# Sheet2.net
KiCad netlist of a schematic drawn in Altium Designer
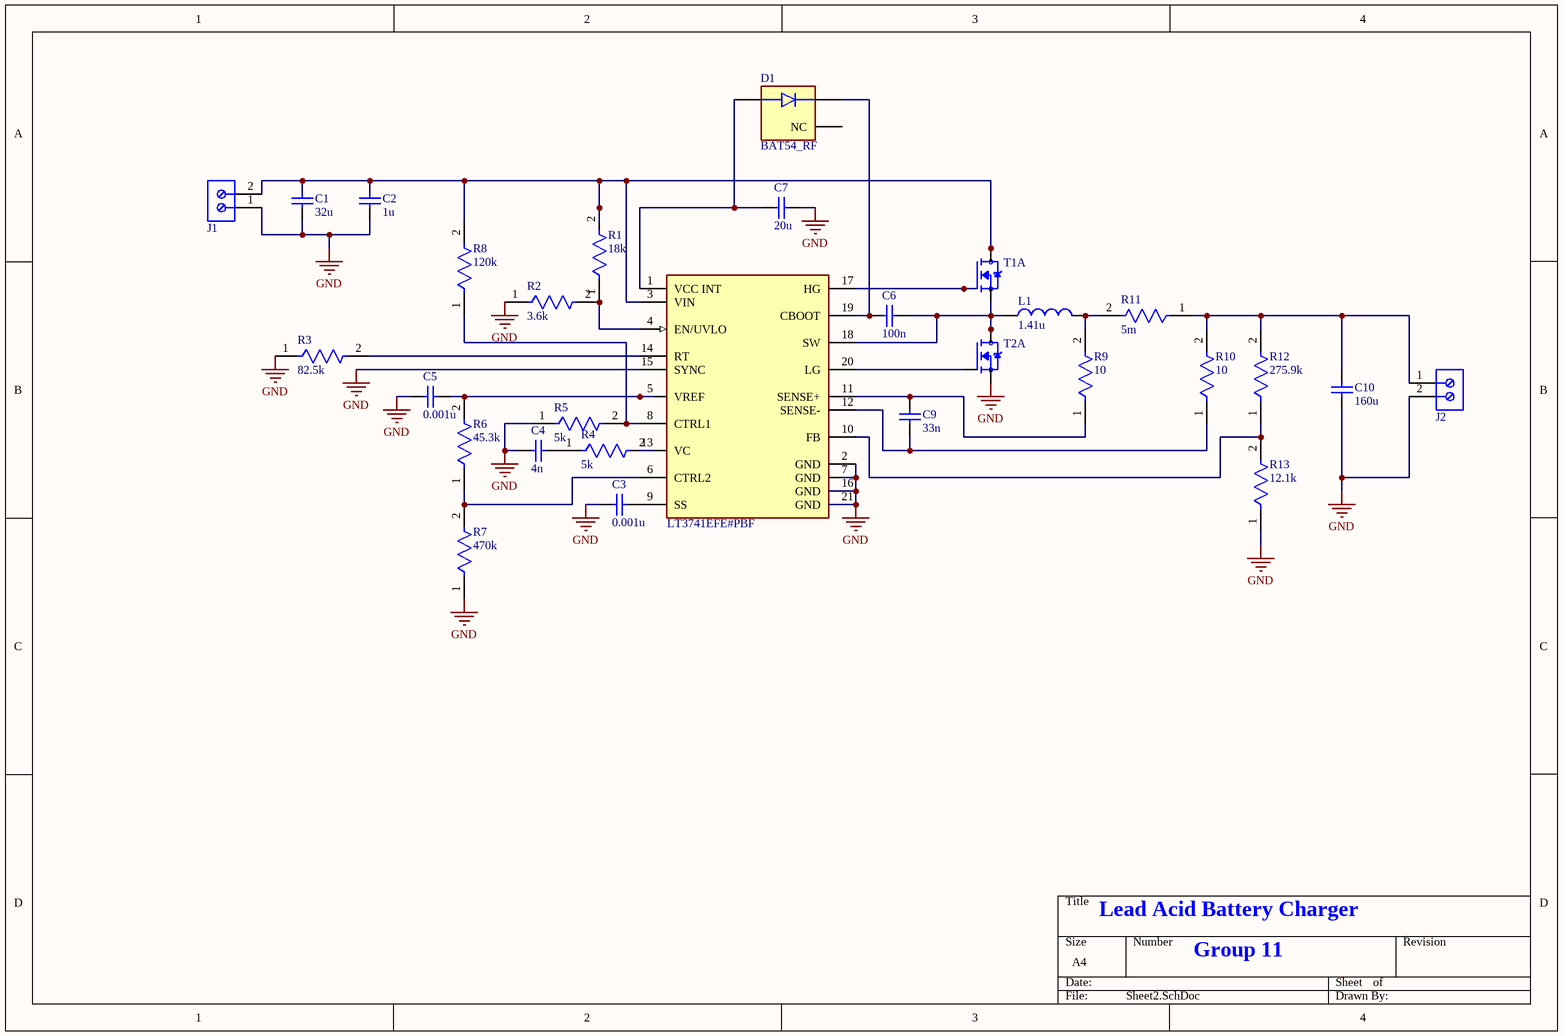
[diagram p0: Sheet2.SchDoc]

(export (version "E")
  (design (tool "Eeschema 10.0.6"))
  (components
    (comp (ref "C1")
      (value "C315C100J2G5TA")
      (footprint "KEMT-C315-THT-2")
      (description "Capacitor, Ceramic, 10 pF, +/-5 %, 200 V, 2-Pin THD, RoHS, Bulk")
      (fields (field (name "CAPACITANCE") "32u"))
      (libsource (lib "Altium Content Vault") (part "CAP-NP-2"))
    )
    (comp (ref "C2")
      (value "C315C100J2G5TA")
      (footprint "KEMT-C315-THT-2")
      (description "Capacitor, Ceramic, 10 pF, +/-5 %, 200 V, 2-Pin THD, RoHS, Bulk")
      (fields (field (name "CAPACITANCE") "1u"))
      (libsource (lib "Altium Content Vault") (part "CAP-NP-2"))
    )
    (comp (ref "C3")
      (value "C315C100J2G5TA")
      (footprint "KEMT-C315-THT-2")
      (description "Capacitor, Ceramic, 10 pF, +/-5 %, 200 V, 2-Pin THD, RoHS, Bulk")
      (fields (field (name "CAPACITANCE") "0.001u"))
      (libsource (lib "Altium Content Vault") (part "CAP-NP-2"))
    )
    (comp (ref "C4")
      (value "C315C100J2G5TA")
      (footprint "KEMT-C315-THT-2")
      (description "Capacitor, Ceramic, 10 pF, +/-5 %, 200 V, 2-Pin THD, RoHS, Bulk")
      (fields (field (name "CAPACITANCE") "4n"))
      (libsource (lib "Altium Content Vault") (part "CAP-NP-2"))
    )
    (comp (ref "C5")
      (value "C315C100J2G5TA")
      (footprint "KEMT-C315-THT-2")
      (description "Capacitor, Ceramic, 10 pF, +/-5 %, 200 V, 2-Pin THD, RoHS, Bulk")
      (fields (field (name "CAPACITANCE") "0.001u"))
      (libsource (lib "Altium Content Vault") (part "CAP-NP-2"))
    )
    (comp (ref "C6")
      (value "C315C100J2G5TA")
      (footprint "KEMT-C315-THT-2")
      (description "Capacitor, Ceramic, 10 pF, +/-5 %, 200 V, 2-Pin THD, RoHS, Bulk")
      (fields (field (name "CAPACITANCE") "100n"))
      (libsource (lib "Altium Content Vault") (part "CAP-NP-2"))
    )
    (comp (ref "C7")
      (value "C315C100J2G5TA")
      (footprint "KEMT-C315-THT-2")
      (description "Capacitor, Ceramic, 10 pF, +/-5 %, 200 V, 2-Pin THD, RoHS, Bulk")
      (fields (field (name "CAPACITANCE") "20u"))
      (libsource (lib "Altium Content Vault") (part "CAP-NP-2"))
    )
    (comp (ref "C9")
      (value "C315C100J2G5TA")
      (footprint "KEMT-C315-THT-2")
      (description "Capacitor, Ceramic, 10 pF, +/-5 %, 200 V, 2-Pin THD, RoHS, Bulk")
      (fields (field (name "CAPACITANCE") "33n"))
      (libsource (lib "Altium Content Vault") (part "CAP-NP-2"))
    )
    (comp (ref "C10")
      (value "C315C100J2G5TA")
      (footprint "KEMT-C315-THT-2")
      (description "Capacitor, Ceramic, 10 pF, +/-5 %, 200 V, 2-Pin THD, RoHS, Bulk")
      (fields (field (name "CAPACITANCE") "160u"))
      (libsource (lib "Altium Content Vault") (part "CAP-NP-2"))
    )
    (comp (ref "D1")
      (value "BAT54_RF")
      (footprint "SOT95P237X112-3N")
      (libsource (lib "BAT54_RF") (part "BAT54_RF"))
    )
    (comp (ref "J1")
      (value "1725656")
      (footprint "PHOE-1725656-2")
      (description "Male Header, Pitch 2.54 mm, 1 x 2 Position, Height 9 mm, Tail Length 3.5 mm")
      (fields (field (name "MANUFACTURER") "Phoenix Contact"))
      (libsource (lib "Altium Content Vault") (part "CN-1P-F-TB2"))
    )
    (comp (ref "J2")
      (value "1725656")
      (footprint "PHOE-1725656-2")
      (description "Male Header, Pitch 2.54 mm, 1 x 2 Position, Height 9 mm, Tail Length 3.5 mm")
      (fields (field (name "MANUFACTURER") "Phoenix Contact"))
      (libsource (lib "Altium Content Vault") (part "CN-1P-F-TB2"))
    )
    (comp (ref "L1")
      (value "7443551131")
      (footprint "IND_7443551131")
      (description "13ÂµH Shielded Wirewound Inductor 10A 11.2mOhm Nonstandard")
      (fields (field (name "MF") "Wurth Electronics") (field (name "INDUCTANCE") "1.41u"))
      (libsource (lib "7443551131") (part "7443551131"))
    )
    (comp (ref "q2etpo")
      (value "LT3741EFE#PBF")
      (footprint "FP-FE-20-05-08-1663-CB-IPC_C")
      (description "IC REG CTRLR BUCK 20TSSOP")
      (libsource (lib "Altium Content Vault") (part "060a2fb32948f8c97f943a762166035"))
    )
    (comp (ref "R1")
      (value "15FR010E")
      (footprint "FP-15FR010E-MFG")
      (description "RES 0.01 OHM 5W 1% AXIAL")
      (fields (field (name "RESISTANCE") "18k") (field (name "TOLERANCE") "1%"))
      (libsource (lib "Altium Content Vault") (part "1029c3af85768c4190bb7ad29bc67b5"))
    )
    (comp (ref "R2")
      (value "15FR010E")
      (footprint "FP-15FR010E-MFG")
      (description "RES 0.01 OHM 5W 1% AXIAL")
      (fields (field (name "RESISTANCE") "3.6k") (field (name "TOLERANCE") "1%"))
      (libsource (lib "Altium Content Vault") (part "1029c3af85768c4190bb7ad29bc67b5"))
    )
    (comp (ref "R3")
      (value "15FR010E")
      (footprint "FP-15FR010E-MFG")
      (description "RES 0.01 OHM 5W 1% AXIAL")
      (fields (field (name "RESISTANCE") "82.5k") (field (name "TOLERANCE") "1%"))
      (libsource (lib "Altium Content Vault") (part "1029c3af85768c4190bb7ad29bc67b5"))
    )
    (comp (ref "R4")
      (value "15FR010E")
      (footprint "FP-15FR010E-MFG")
      (description "RES 0.01 OHM 5W 1% AXIAL")
      (fields (field (name "RESISTANCE") "5k") (field (name "TOLERANCE") "1%"))
      (libsource (lib "Altium Content Vault") (part "1029c3af85768c4190bb7ad29bc67b5"))
    )
    (comp (ref "R5")
      (value "15FR010E")
      (footprint "FP-15FR010E-MFG")
      (description "RES 0.01 OHM 5W 1% AXIAL")
      (fields (field (name "RESISTANCE") "5k") (field (name "TOLERANCE") "1%"))
      (libsource (lib "Altium Content Vault") (part "1029c3af85768c4190bb7ad29bc67b5"))
    )
    (comp (ref "R6")
      (value "15FR010E")
      (footprint "FP-15FR010E-MFG")
      (description "RES 0.01 OHM 5W 1% AXIAL")
      (fields (field (name "RESISTANCE") "45.3k") (field (name "TOLERANCE") "1%"))
      (libsource (lib "Altium Content Vault") (part "1029c3af85768c4190bb7ad29bc67b5"))
    )
    (comp (ref "R7")
      (value "15FR010E")
      (footprint "FP-15FR010E-MFG")
      (description "RES 0.01 OHM 5W 1% AXIAL")
      (fields (field (name "RESISTANCE") "470k") (field (name "TOLERANCE") "1%"))
      (libsource (lib "Altium Content Vault") (part "1029c3af85768c4190bb7ad29bc67b5"))
    )
    (comp (ref "R8")
      (value "15FR010E")
      (footprint "FP-15FR010E-MFG")
      (description "RES 0.01 OHM 5W 1% AXIAL")
      (fields (field (name "RESISTANCE") "120k") (field (name "TOLERANCE") "1%"))
      (libsource (lib "Altium Content Vault") (part "1029c3af85768c4190bb7ad29bc67b5"))
    )
    (comp (ref "R9")
      (value "15FR010E")
      (footprint "FP-15FR010E-MFG")
      (description "RES 0.01 OHM 5W 1% AXIAL")
      (fields (field (name "RESISTANCE") "10") (field (name "TOLERANCE") "1%"))
      (libsource (lib "Altium Content Vault") (part "1029c3af85768c4190bb7ad29bc67b5"))
    )
    (comp (ref "R10")
      (value "15FR010E")
      (footprint "FP-15FR010E-MFG")
      (description "RES 0.01 OHM 5W 1% AXIAL")
      (fields (field (name "RESISTANCE") "10") (field (name "TOLERANCE") "1%"))
      (libsource (lib "Altium Content Vault") (part "1029c3af85768c4190bb7ad29bc67b5"))
    )
    (comp (ref "R11")
      (value "15FR010E")
      (footprint "FP-15FR010E-MFG")
      (description "RES 0.01 OHM 5W 1% AXIAL")
      (fields (field (name "RESISTANCE") "5m") (field (name "TOLERANCE") "1%"))
      (libsource (lib "Altium Content Vault") (part "1029c3af85768c4190bb7ad29bc67b5"))
    )
    (comp (ref "R12")
      (value "15FR010E")
      (footprint "FP-15FR010E-MFG")
      (description "RES 0.01 OHM 5W 1% AXIAL")
      (fields (field (name "RESISTANCE") "275.9k") (field (name "TOLERANCE") "1%"))
      (libsource (lib "Altium Content Vault") (part "1029c3af85768c4190bb7ad29bc67b5"))
    )
    (comp (ref "R13")
      (value "15FR010E")
      (footprint "FP-15FR010E-MFG")
      (description "RES 0.01 OHM 5W 1% AXIAL")
      (fields (field (name "RESISTANCE") "12.1k") (field (name "TOLERANCE") "1%"))
      (libsource (lib "Altium Content Vault") (part "1029c3af85768c4190bb7ad29bc67b5"))
    )
    (comp (ref "T1")
      (value "CSD88539ND")
      (footprint "SOIC127P600X175-8N")
      (description "60V, N ch NexFET MOSFET, dual SO-8, 28mOhm 8-SOIC -55 to 150")
      (libsource (lib "CSD88539ND") (part "CSD88539ND"))
    )
    (comp (ref "T2")
      (value "CSD88539ND")
      (footprint "SOIC127P600X175-8N")
      (description "60V, N ch NexFET MOSFET, dual SO-8, 28mOhm 8-SOIC -55 to 150")
      (libsource (lib "CSD88539ND") (part "CSD88539ND"))
    )
  )
  (nets
    (net (code "1") (name "GND") (class "Default")
      (node (ref "C1") (pin "1") (pinfunction "1_1") (pintype "passive"))
      (node (ref "C10") (pin "1") (pinfunction "1_1") (pintype "passive"))
      (node (ref "C2") (pin "1") (pinfunction "1_1") (pintype "passive"))
      (node (ref "C3") (pin "1") (pinfunction "1_1") (pintype "passive"))
      (node (ref "C4") (pin "1") (pinfunction "1_1") (pintype "passive"))
      (node (ref "C5") (pin "1") (pinfunction "1_1") (pintype "passive"))
      (node (ref "C7") (pin "1") (pinfunction "1_1") (pintype "passive"))
      (node (ref "J1") (pin "1") (pinfunction "1_1") (pintype "passive"))
      (node (ref "J2") (pin "2") (pinfunction "2_2") (pintype "passive"))
      (node (ref "R13") (pin "1") (pinfunction "1_1") (pintype "passive"))
      (node (ref "R2") (pin "1") (pinfunction "1_1") (pintype "passive"))
      (node (ref "R3") (pin "1") (pinfunction "1_1") (pintype "passive"))
      (node (ref "R5") (pin "1") (pinfunction "1_1") (pintype "passive"))
      (node (ref "R7") (pin "1") (pinfunction "1_1") (pintype "passive"))
      (node (ref "T2") (pin "1") (pinfunction "S1_1") (pintype "passive"))
      (node (ref "q2etpo") (pin "15") (pinfunction "SYNC_15") (pintype "passive"))
      (node (ref "q2etpo") (pin "16") (pinfunction "GND_16") (pintype "power_in"))
      (node (ref "q2etpo") (pin "2") (pinfunction "GND_2") (pintype "power_in"))
      (node (ref "q2etpo") (pin "21") (pinfunction "GND_21") (pintype "power_in"))
      (node (ref "q2etpo") (pin "7") (pinfunction "GND_7") (pintype "power_in"))
    )
    (net (code "2") (name "Net-(C4-Pad2)") (class "Default")
      (node (ref "C4") (pin "2") (pinfunction "2_2") (pintype "passive"))
      (node (ref "R4") (pin "1") (pinfunction "1_1") (pintype "passive"))
    )
    (net (code "3") (name "Net-(C10-Pad2)") (class "Default")
      (node (ref "C10") (pin "2") (pinfunction "2_2") (pintype "passive"))
      (node (ref "J2") (pin "1") (pinfunction "1_1") (pintype "passive"))
      (node (ref "R10") (pin "2") (pinfunction "2_2") (pintype "passive"))
      (node (ref "R11") (pin "1") (pinfunction "1_1") (pintype "passive"))
      (node (ref "R12") (pin "2") (pinfunction "2_2") (pintype "passive"))
    )
    (net (code "4") (name "Net-(D1-A)") (class "Default")
      (node (ref "C7") (pin "2") (pinfunction "2_2") (pintype "passive"))
      (node (ref "D1") (pin "1") (pinfunction "A_1") (pintype "passive"))
      (node (ref "q2etpo") (pin "1") (pinfunction "VCC_INT_1") (pintype "power_in"))
    )
    (net (code "5") (name "Net-(D1-K)") (class "Default")
      (node (ref "C6") (pin "2") (pinfunction "2_2") (pintype "passive"))
      (node (ref "D1") (pin "3") (pinfunction "K_3") (pintype "passive"))
      (node (ref "q2etpo") (pin "19") (pinfunction "CBOOT_19") (pintype "passive"))
    )
    (net (code "6") (name "Net-(L1-Pad2)") (class "Default")
      (node (ref "L1") (pin "2") (pinfunction "2_2") (pintype "passive"))
      (node (ref "R11") (pin "2") (pinfunction "2_2") (pintype "passive"))
      (node (ref "R9") (pin "2") (pinfunction "2_2") (pintype "passive"))
    )
    (net (code "7") (name "Net-(T1A-G1)") (class "Default")
      (node (ref "T1") (pin "2") (pinfunction "G1_2") (pintype "passive"))
      (node (ref "q2etpo") (pin "17") (pinfunction "HG_17") (pintype "passive"))
    )
    (net (code "8") (name "Net-(T1A-S1)") (class "Default")
      (node (ref "C6") (pin "1") (pinfunction "1_1") (pintype "passive"))
      (node (ref "L1") (pin "1") (pinfunction "1_1") (pintype "passive"))
      (node (ref "T1") (pin "1") (pinfunction "S1_1") (pintype "passive"))
      (node (ref "T2") (pin "7") (pinfunction "D1_7") (pintype "passive"))
      (node (ref "T2") (pin "8") (pinfunction "D1_8") (pintype "passive"))
      (node (ref "q2etpo") (pin "18") (pinfunction "SW_18") (pintype "passive"))
    )
    (net (code "9") (name "Net-(T2A-G1)") (class "Default")
      (node (ref "T2") (pin "2") (pinfunction "G1_2") (pintype "passive"))
      (node (ref "q2etpo") (pin "20") (pinfunction "LG_20") (pintype "passive"))
    )
    (net (code "10") (name "Net-(q2etpo-CTRL1)") (class "Default")
      (node (ref "R5") (pin "2") (pinfunction "2_2") (pintype "passive"))
      (node (ref "R8") (pin "1") (pinfunction "1_1") (pintype "passive"))
      (node (ref "q2etpo") (pin "8") (pinfunction "CTRL1_8") (pintype "passive"))
    )
    (net (code "11") (name "Net-(q2etpo-CTRL2)") (class "Default")
      (node (ref "R6") (pin "1") (pinfunction "1_1") (pintype "passive"))
      (node (ref "R7") (pin "2") (pinfunction "2_2") (pintype "passive"))
      (node (ref "q2etpo") (pin "6") (pinfunction "CTRL2_6") (pintype "passive"))
    )
    (net (code "12") (name "Net-(q2etpo-EN{slash}UVLO)") (class "Default")
      (node (ref "R1") (pin "1") (pinfunction "1_1") (pintype "passive"))
      (node (ref "R2") (pin "2") (pinfunction "2_2") (pintype "passive"))
      (node (ref "q2etpo") (pin "4") (pinfunction "EN/UVLO_4") (pintype "input"))
    )
    (net (code "13") (name "Net-(q2etpo-FB)") (class "Default")
      (node (ref "R12") (pin "1") (pinfunction "1_1") (pintype "passive"))
      (node (ref "R13") (pin "2") (pinfunction "2_2") (pintype "passive"))
      (node (ref "q2etpo") (pin "10") (pinfunction "FB_10") (pintype "passive"))
    )
    (net (code "14") (name "Net-(q2etpo-RT)") (class "Default")
      (node (ref "R3") (pin "2") (pinfunction "2_2") (pintype "passive"))
      (node (ref "q2etpo") (pin "14") (pinfunction "RT_14") (pintype "passive"))
    )
    (net (code "15") (name "Net-(q2etpo-SENSE+)") (class "Default")
      (node (ref "C9") (pin "1") (pinfunction "1_1") (pintype "passive"))
      (node (ref "R9") (pin "1") (pinfunction "1_1") (pintype "passive"))
      (node (ref "q2etpo") (pin "11") (pinfunction "SENSE+_11") (pintype "passive"))
    )
    (net (code "16") (name "Net-(q2etpo-SENSE-)") (class "Default")
      (node (ref "C9") (pin "2") (pinfunction "2_2") (pintype "passive"))
      (node (ref "R10") (pin "1") (pinfunction "1_1") (pintype "passive"))
      (node (ref "q2etpo") (pin "12") (pinfunction "SENSE-_12") (pintype "passive"))
    )
    (net (code "17") (name "Net-(q2etpo-SS)") (class "Default")
      (node (ref "C3") (pin "2") (pinfunction "2_2") (pintype "passive"))
      (node (ref "q2etpo") (pin "9") (pinfunction "SS_9") (pintype "passive"))
    )
    (net (code "18") (name "Net-(q2etpo-VC)") (class "Default")
      (node (ref "R4") (pin "2") (pinfunction "2_2") (pintype "passive"))
      (node (ref "q2etpo") (pin "13") (pinfunction "VC_13") (pintype "passive"))
    )
    (net (code "19") (name "Net-(q2etpo-VIN)") (class "Default")
      (node (ref "C1") (pin "2") (pinfunction "2_2") (pintype "passive"))
      (node (ref "C2") (pin "2") (pinfunction "2_2") (pintype "passive"))
      (node (ref "J1") (pin "2") (pinfunction "2_2") (pintype "passive"))
      (node (ref "R1") (pin "2") (pinfunction "2_2") (pintype "passive"))
      (node (ref "R8") (pin "2") (pinfunction "2_2") (pintype "passive"))
      (node (ref "T1") (pin "7") (pinfunction "D1_7") (pintype "passive"))
      (node (ref "T1") (pin "8") (pinfunction "D1_8") (pintype "passive"))
      (node (ref "q2etpo") (pin "3") (pinfunction "VIN_3") (pintype "power_in"))
    )
    (net (code "20") (name "Net-(q2etpo-VREF)") (class "Default")
      (node (ref "C5") (pin "2") (pinfunction "2_2") (pintype "passive"))
      (node (ref "R6") (pin "2") (pinfunction "2_2") (pintype "passive"))
      (node (ref "q2etpo") (pin "5") (pinfunction "VREF_5") (pintype "passive"))
    )
    (net (code "21") (name "unconnected-(D1-NC-Pad2)") (class "Default")
      (node (ref "D1") (pin "2") (pinfunction "NC_2") (pintype "passive"))
    )
  )
)
